# design.net
KiCad netlist of a schematic drawn in Altium Designer
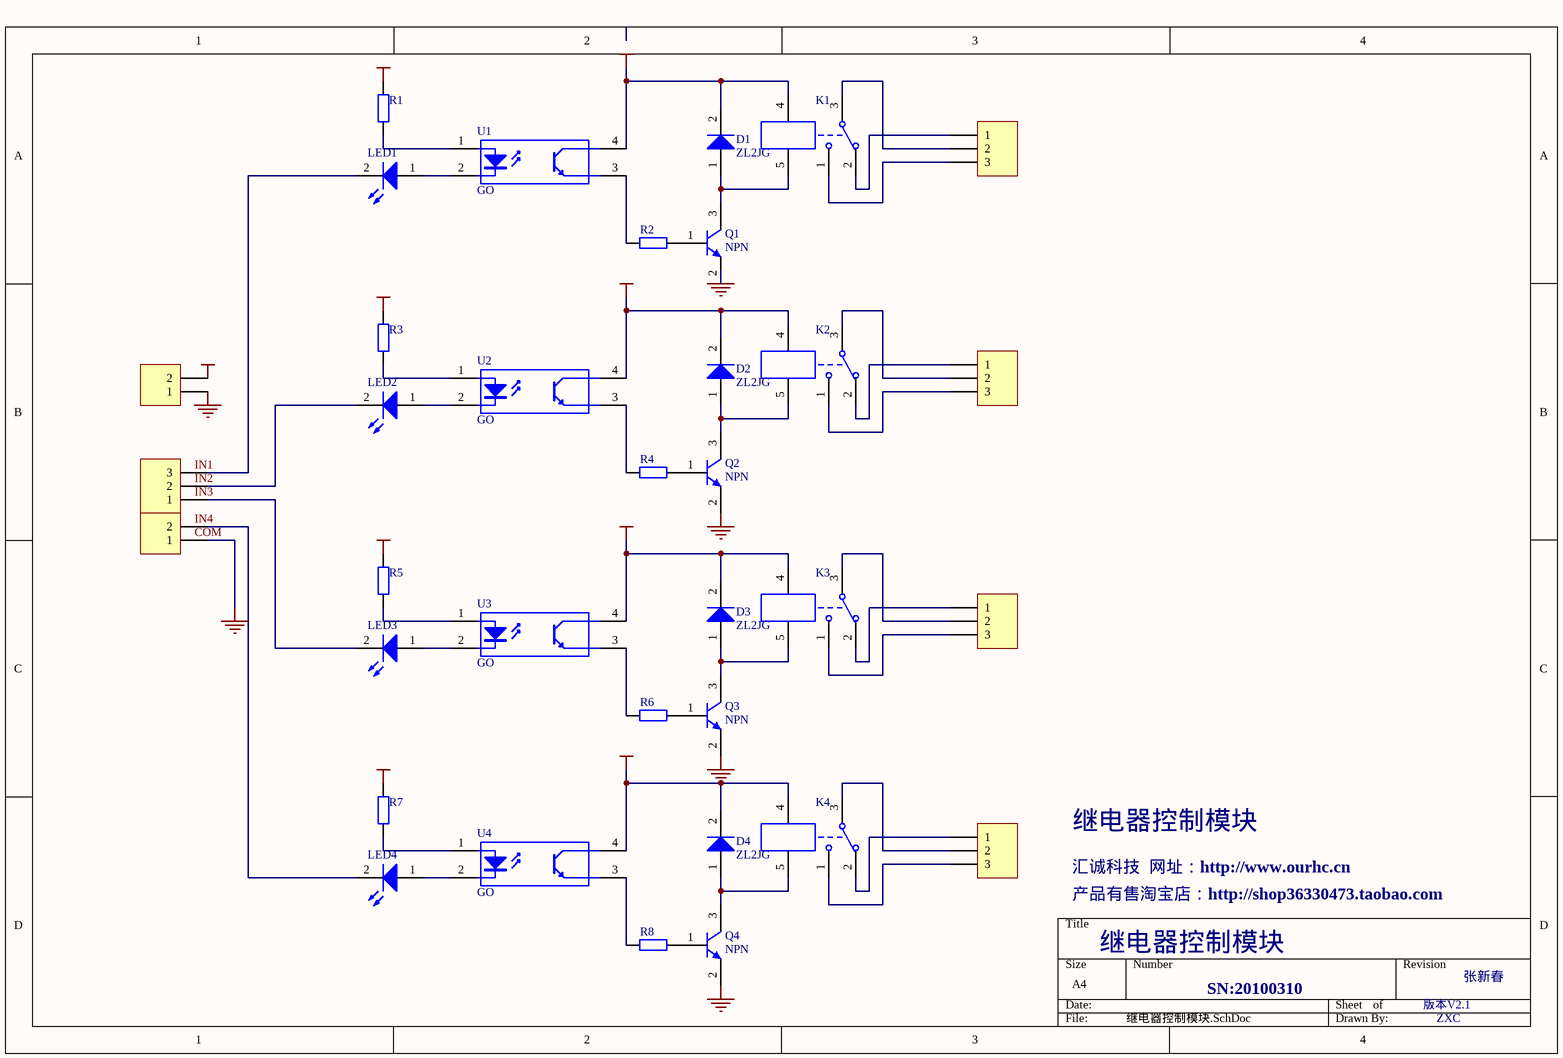
[diagram p0: 继电器控制模块.SchDoc]

(export (version "E")
  (design (tool "Eeschema 10.0.6"))
  (components
    (comp (ref "D1")
      (value "ZL2JG")
      (footprint "TPDR")
      (description "整流二极管")
      (fields (field (name "PUBLISHER") "Altium Limited"))
      (libsource (lib "zxcourhc") (part "ZL2JG"))
    )
    (comp (ref "D2")
      (value "ZL2JG")
      (footprint "TPDR")
      (description "整流二极管")
      (fields (field (name "PUBLISHER") "Altium Limited"))
      (libsource (lib "zxcourhc") (part "ZL2JG"))
    )
    (comp (ref "D3")
      (value "ZL2JG")
      (footprint "TPDR")
      (description "整流二极管")
      (fields (field (name "PUBLISHER") "Altium Limited"))
      (libsource (lib "zxcourhc") (part "ZL2JG"))
    )
    (comp (ref "D4")
      (value "ZL2JG")
      (footprint "TPDR")
      (description "整流二极管")
      (fields (field (name "PUBLISHER") "Altium Limited"))
      (libsource (lib "zxcourhc") (part "ZL2JG"))
    )
    (comp (ref "IN1")
      (value "PZ_3")
      (footprint "JK128_3")
      (description "排针——3")
      (fields (field (name "PUBLISHER") "Altium Limited"))
      (libsource (lib "zxcourhc") (part "PZ_3"))
    )
    (comp (ref "IN2")
      (value "PZ_2")
      (footprint "JK128_2")
      (description "排针——2")
      (fields (field (name "PUBLISHER") "Altium Limited"))
      (libsource (lib "zxcourhc") (part "PZ_2"))
    )
    (comp (ref "K1")
      (value "JDQYCK")
      (footprint "JQC-3F/T73")
      (description "继电器——1常开1常闭")
      (fields (field (name "PUBLISHER") "Altium Limited"))
      (libsource (lib "zxcourhc") (part "JDQYCK"))
    )
    (comp (ref "K2")
      (value "JDQYCK")
      (footprint "JQC-3F/T73")
      (description "继电器——1常开1常闭")
      (fields (field (name "PUBLISHER") "Altium Limited"))
      (libsource (lib "zxcourhc") (part "JDQYCK"))
    )
    (comp (ref "K3")
      (value "JDQYCK")
      (footprint "JQC-3F/T73")
      (description "继电器——1常开1常闭")
      (fields (field (name "PUBLISHER") "Altium Limited"))
      (libsource (lib "zxcourhc") (part "JDQYCK"))
    )
    (comp (ref "K4")
      (value "JDQYCK")
      (footprint "JQC-3F/T73")
      (description "继电器——1常开1常闭")
      (fields (field (name "PUBLISHER") "Altium Limited"))
      (libsource (lib "zxcourhc") (part "JDQYCK"))
    )
    (comp (ref "LED1")
      (value "~")
      (footprint "TP-0805-D")
      (description "发光二极管")
      (fields (field (name "PUBLISHER") "Altium Limited"))
      (libsource (lib "zxcourhc") (part "LED"))
    )
    (comp (ref "LED2")
      (value "~")
      (footprint "TP-0805-D")
      (description "发光二极管")
      (fields (field (name "PUBLISHER") "Altium Limited"))
      (libsource (lib "zxcourhc") (part "LED"))
    )
    (comp (ref "LED3")
      (value "~")
      (footprint "TP-0805-D")
      (description "发光二极管")
      (fields (field (name "PUBLISHER") "Altium Limited"))
      (libsource (lib "zxcourhc") (part "LED"))
    )
    (comp (ref "LED4")
      (value "~")
      (footprint "TP-0805-D")
      (description "发光二极管")
      (fields (field (name "PUBLISHER") "Altium Limited"))
      (libsource (lib "zxcourhc") (part "LED"))
    )
    (comp (ref "OUT1")
      (value "PZ_3")
      (footprint "JK128_3")
      (description "排针——3")
      (fields (field (name "PUBLISHER") "Altium Limited"))
      (libsource (lib "") (part "PZ_3_1"))
    )
    (comp (ref "OUT2")
      (value "PZ_3")
      (footprint "JK128_3")
      (description "排针——3")
      (fields (field (name "PUBLISHER") "Altium Limited"))
      (libsource (lib "") (part "PZ_3_1"))
    )
    (comp (ref "OUT3")
      (value "PZ_3")
      (footprint "JK128_3")
      (description "排针——3")
      (fields (field (name "PUBLISHER") "Altium Limited"))
      (libsource (lib "") (part "PZ_3_1"))
    )
    (comp (ref "OUT4")
      (value "PZ_3")
      (footprint "JK128_3")
      (description "排针——3")
      (fields (field (name "PUBLISHER") "Altium Limited"))
      (libsource (lib "") (part "PZ_3_1"))
    )
    (comp (ref "POWER")
      (value "PZ_2")
      (footprint "JK128_2")
      (description "排针——2")
      (fields (field (name "PUBLISHER") "Altium Limited"))
      (libsource (lib "zxcourhc") (part "PZ_2"))
    )
    (comp (ref "Q1")
      (value "NPN")
      (footprint "SO-G3")
      (description "NPN Bipolar Transistor")
      (fields (field (name "PUBLISHER") "Altium Limited"))
      (libsource (lib "Miscellaneous Devices") (part "NPN"))
    )
    (comp (ref "Q2")
      (value "NPN")
      (footprint "SO-G3")
      (description "NPN Bipolar Transistor")
      (fields (field (name "PUBLISHER") "Altium Limited"))
      (libsource (lib "Miscellaneous Devices") (part "NPN"))
    )
    (comp (ref "Q3")
      (value "NPN")
      (footprint "SO-G3")
      (description "NPN Bipolar Transistor")
      (fields (field (name "PUBLISHER") "Altium Limited"))
      (libsource (lib "Miscellaneous Devices") (part "NPN"))
    )
    (comp (ref "Q4")
      (value "NPN")
      (footprint "SO-G3")
      (description "NPN Bipolar Transistor")
      (fields (field (name "PUBLISHER") "Altium Limited"))
      (libsource (lib "Miscellaneous Devices") (part "NPN"))
    )
    (comp (ref "R1")
      (value "Res")
      (footprint "TP-0805-R")
      (description "电阻")
      (fields (field (name "PUBLISHER") "Altium Limited"))
      (libsource (lib "zxcourhc") (part "Res"))
    )
    (comp (ref "R2")
      (value "Res")
      (footprint "TP-0805-R")
      (description "电阻")
      (fields (field (name "PUBLISHER") "Altium Limited"))
      (libsource (lib "") (part "Res_1"))
    )
    (comp (ref "R3")
      (value "Res")
      (footprint "TP-0805-R")
      (description "电阻")
      (fields (field (name "PUBLISHER") "Altium Limited"))
      (libsource (lib "zxcourhc") (part "Res"))
    )
    (comp (ref "R4")
      (value "Res")
      (footprint "TP-0805-R")
      (description "电阻")
      (fields (field (name "PUBLISHER") "Altium Limited"))
      (libsource (lib "") (part "Res_1"))
    )
    (comp (ref "R5")
      (value "Res")
      (footprint "TP-0805-R")
      (description "电阻")
      (fields (field (name "PUBLISHER") "Altium Limited"))
      (libsource (lib "zxcourhc") (part "Res"))
    )
    (comp (ref "R6")
      (value "Res")
      (footprint "TP-0805-R")
      (description "电阻")
      (fields (field (name "PUBLISHER") "Altium Limited"))
      (libsource (lib "") (part "Res_1"))
    )
    (comp (ref "R7")
      (value "Res")
      (footprint "TP-0805-R")
      (description "电阻")
      (fields (field (name "PUBLISHER") "Altium Limited"))
      (libsource (lib "zxcourhc") (part "Res"))
    )
    (comp (ref "R8")
      (value "Res")
      (footprint "TP-0805-R")
      (description "电阻")
      (fields (field (name "PUBLISHER") "Altium Limited"))
      (libsource (lib "") (part "Res_1"))
    )
    (comp (ref "U1")
      (value "GO")
      (footprint "DIP-4")
      (description "光耦")
      (fields (field (name "PUBLISHER") "Altium Limited"))
      (libsource (lib "zxcourhc") (part "GO"))
    )
    (comp (ref "U2")
      (value "GO")
      (footprint "DIP-4")
      (description "光耦")
      (fields (field (name "PUBLISHER") "Altium Limited"))
      (libsource (lib "zxcourhc") (part "GO"))
    )
    (comp (ref "U3")
      (value "GO")
      (footprint "DIP-4")
      (description "光耦")
      (fields (field (name "PUBLISHER") "Altium Limited"))
      (libsource (lib "zxcourhc") (part "GO"))
    )
    (comp (ref "U4")
      (value "GO")
      (footprint "DIP-4")
      (description "光耦")
      (fields (field (name "PUBLISHER") "Altium Limited"))
      (libsource (lib "zxcourhc") (part "GO"))
    )
  )
  (nets
    (net (code "6") (name "GND") (class "Default")
      (node (ref "IN2") (pin "1") (pinfunction "1_1") (pintype "passive"))
      (node (ref "POWER") (pin "1") (pinfunction "1_1") (pintype "passive"))
      (node (ref "Q1") (pin "2") (pinfunction "E_2") (pintype "passive"))
      (node (ref "Q2") (pin "2") (pinfunction "E_2") (pintype "passive"))
      (node (ref "Q3") (pin "2") (pinfunction "E_2") (pintype "passive"))
      (node (ref "Q4") (pin "2") (pinfunction "E_2") (pintype "passive"))
    )
    (net (code "7") (name "Net-(D1-A)") (class "Default")
      (node (ref "D1") (pin "1") (pinfunction "A_1") (pintype "passive"))
      (node (ref "K1") (pin "5") (pinfunction "5_5") (pintype "passive"))
      (node (ref "Q1") (pin "3") (pinfunction "C_3") (pintype "passive"))
    )
    (net (code "8") (name "Net-(D2-A)") (class "Default")
      (node (ref "D2") (pin "1") (pinfunction "A_1") (pintype "passive"))
      (node (ref "K2") (pin "5") (pinfunction "5_5") (pintype "passive"))
      (node (ref "Q2") (pin "3") (pinfunction "C_3") (pintype "passive"))
    )
    (net (code "9") (name "Net-(D3-A)") (class "Default")
      (node (ref "D3") (pin "1") (pinfunction "A_1") (pintype "passive"))
      (node (ref "K3") (pin "5") (pinfunction "5_5") (pintype "passive"))
      (node (ref "Q3") (pin "3") (pinfunction "C_3") (pintype "passive"))
    )
    (net (code "10") (name "Net-(D4-A)") (class "Default")
      (node (ref "D4") (pin "1") (pinfunction "A_1") (pintype "passive"))
      (node (ref "K4") (pin "5") (pinfunction "5_5") (pintype "passive"))
      (node (ref "Q4") (pin "3") (pinfunction "C_3") (pintype "passive"))
    )
    (net (code "11") (name "Net-(K1-Pad1)") (class "Default")
      (node (ref "K1") (pin "1") (pinfunction "1_1") (pintype "passive"))
      (node (ref "OUT1") (pin "3") (pinfunction "3_3") (pintype "passive"))
    )
    (net (code "12") (name "Net-(K1-Pad2)") (class "Default")
      (node (ref "K1") (pin "2") (pinfunction "2_2") (pintype "passive"))
      (node (ref "OUT1") (pin "1") (pinfunction "1_1") (pintype "passive"))
    )
    (net (code "13") (name "Net-(K1-Pad3)") (class "Default")
      (node (ref "K1") (pin "3") (pinfunction "3_3") (pintype "passive"))
      (node (ref "OUT1") (pin "2") (pinfunction "2_2") (pintype "passive"))
    )
    (net (code "14") (name "Net-(K2-Pad1)") (class "Default")
      (node (ref "K2") (pin "1") (pinfunction "1_1") (pintype "passive"))
      (node (ref "OUT2") (pin "3") (pinfunction "3_3") (pintype "passive"))
    )
    (net (code "15") (name "Net-(K2-Pad2)") (class "Default")
      (node (ref "K2") (pin "2") (pinfunction "2_2") (pintype "passive"))
      (node (ref "OUT2") (pin "1") (pinfunction "1_1") (pintype "passive"))
    )
    (net (code "16") (name "Net-(K2-Pad3)") (class "Default")
      (node (ref "K2") (pin "3") (pinfunction "3_3") (pintype "passive"))
      (node (ref "OUT2") (pin "2") (pinfunction "2_2") (pintype "passive"))
    )
    (net (code "17") (name "Net-(K3-Pad1)") (class "Default")
      (node (ref "K3") (pin "1") (pinfunction "1_1") (pintype "passive"))
      (node (ref "OUT3") (pin "3") (pinfunction "3_3") (pintype "passive"))
    )
    (net (code "18") (name "Net-(K3-Pad2)") (class "Default")
      (node (ref "K3") (pin "2") (pinfunction "2_2") (pintype "passive"))
      (node (ref "OUT3") (pin "1") (pinfunction "1_1") (pintype "passive"))
    )
    (net (code "19") (name "Net-(K3-Pad3)") (class "Default")
      (node (ref "K3") (pin "3") (pinfunction "3_3") (pintype "passive"))
      (node (ref "OUT3") (pin "2") (pinfunction "2_2") (pintype "passive"))
    )
    (net (code "20") (name "Net-(K4-Pad1)") (class "Default")
      (node (ref "K4") (pin "1") (pinfunction "1_1") (pintype "passive"))
      (node (ref "OUT4") (pin "3") (pinfunction "3_3") (pintype "passive"))
    )
    (net (code "21") (name "Net-(K4-Pad2)") (class "Default")
      (node (ref "K4") (pin "2") (pinfunction "2_2") (pintype "passive"))
      (node (ref "OUT4") (pin "1") (pinfunction "1_1") (pintype "passive"))
    )
    (net (code "22") (name "Net-(K4-Pad3)") (class "Default")
      (node (ref "K4") (pin "3") (pinfunction "3_3") (pintype "passive"))
      (node (ref "OUT4") (pin "2") (pinfunction "2_2") (pintype "passive"))
    )
    (net (code "23") (name "Net-(LED1-A)") (class "Default")
      (node (ref "LED1") (pin "1") (pinfunction "A_1") (pintype "passive"))
      (node (ref "U1") (pin "2") (pinfunction "K_2") (pintype "passive"))
    )
    (net (code "24") (name "Net-(LED1-K)") (class "Default")
      (node (ref "IN1") (pin "3") (pinfunction "3_3") (pintype "passive"))
      (node (ref "LED1") (pin "2") (pinfunction "K_2") (pintype "passive"))
    )
    (net (code "25") (name "Net-(LED2-A)") (class "Default")
      (node (ref "LED2") (pin "1") (pinfunction "A_1") (pintype "passive"))
      (node (ref "U2") (pin "2") (pinfunction "K_2") (pintype "passive"))
    )
    (net (code "26") (name "Net-(LED2-K)") (class "Default")
      (node (ref "IN1") (pin "2") (pinfunction "2_2") (pintype "passive"))
      (node (ref "LED2") (pin "2") (pinfunction "K_2") (pintype "passive"))
    )
    (net (code "27") (name "Net-(LED3-A)") (class "Default")
      (node (ref "LED3") (pin "1") (pinfunction "A_1") (pintype "passive"))
      (node (ref "U3") (pin "2") (pinfunction "K_2") (pintype "passive"))
    )
    (net (code "28") (name "Net-(LED3-K)") (class "Default")
      (node (ref "IN1") (pin "1") (pinfunction "1_1") (pintype "passive"))
      (node (ref "LED3") (pin "2") (pinfunction "K_2") (pintype "passive"))
    )
    (net (code "29") (name "Net-(LED4-A)") (class "Default")
      (node (ref "LED4") (pin "1") (pinfunction "A_1") (pintype "passive"))
      (node (ref "U4") (pin "2") (pinfunction "K_2") (pintype "passive"))
    )
    (net (code "30") (name "Net-(LED4-K)") (class "Default")
      (node (ref "IN2") (pin "2") (pinfunction "2_2") (pintype "passive"))
      (node (ref "LED4") (pin "2") (pinfunction "K_2") (pintype "passive"))
    )
    (net (code "31") (name "Net-(Q1-B)") (class "Default")
      (node (ref "Q1") (pin "1") (pinfunction "B_1") (pintype "passive"))
      (node (ref "R2") (pin "1") (pinfunction "1_1") (pintype "passive"))
    )
    (net (code "32") (name "Net-(Q2-B)") (class "Default")
      (node (ref "Q2") (pin "1") (pinfunction "B_1") (pintype "passive"))
      (node (ref "R4") (pin "1") (pinfunction "1_1") (pintype "passive"))
    )
    (net (code "33") (name "Net-(Q3-B)") (class "Default")
      (node (ref "Q3") (pin "1") (pinfunction "B_1") (pintype "passive"))
      (node (ref "R6") (pin "1") (pinfunction "1_1") (pintype "passive"))
    )
    (net (code "34") (name "Net-(Q4-B)") (class "Default")
      (node (ref "Q4") (pin "1") (pinfunction "B_1") (pintype "passive"))
      (node (ref "R8") (pin "1") (pinfunction "1_1") (pintype "passive"))
    )
    (net (code "35") (name "Net-(U1-A)") (class "Default")
      (node (ref "R1") (pin "1") (pinfunction "1_1") (pintype "passive"))
      (node (ref "U1") (pin "1") (pinfunction "A_1") (pintype "passive"))
    )
    (net (code "36") (name "Net-(U1-E)") (class "Default")
      (node (ref "R2") (pin "2") (pinfunction "2_2") (pintype "passive"))
      (node (ref "U1") (pin "3") (pinfunction "E_3") (pintype "passive"))
    )
    (net (code "37") (name "Net-(U2-A)") (class "Default")
      (node (ref "R3") (pin "1") (pinfunction "1_1") (pintype "passive"))
      (node (ref "U2") (pin "1") (pinfunction "A_1") (pintype "passive"))
    )
    (net (code "38") (name "Net-(U2-E)") (class "Default")
      (node (ref "R4") (pin "2") (pinfunction "2_2") (pintype "passive"))
      (node (ref "U2") (pin "3") (pinfunction "E_3") (pintype "passive"))
    )
    (net (code "39") (name "Net-(U3-A)") (class "Default")
      (node (ref "R5") (pin "1") (pinfunction "1_1") (pintype "passive"))
      (node (ref "U3") (pin "1") (pinfunction "A_1") (pintype "passive"))
    )
    (net (code "40") (name "Net-(U3-E)") (class "Default")
      (node (ref "R6") (pin "2") (pinfunction "2_2") (pintype "passive"))
      (node (ref "U3") (pin "3") (pinfunction "E_3") (pintype "passive"))
    )
    (net (code "41") (name "Net-(U4-A)") (class "Default")
      (node (ref "R7") (pin "1") (pinfunction "1_1") (pintype "passive"))
      (node (ref "U4") (pin "1") (pinfunction "A_1") (pintype "passive"))
    )
    (net (code "42") (name "Net-(U4-E)") (class "Default")
      (node (ref "R8") (pin "2") (pinfunction "2_2") (pintype "passive"))
      (node (ref "U4") (pin "3") (pinfunction "E_3") (pintype "passive"))
    )
    (net (code "43") (name "VCC") (class "Default")
      (node (ref "D1") (pin "2") (pinfunction "K_2") (pintype "passive"))
      (node (ref "D2") (pin "2") (pinfunction "K_2") (pintype "passive"))
      (node (ref "D3") (pin "2") (pinfunction "K_2") (pintype "passive"))
      (node (ref "D4") (pin "2") (pinfunction "K_2") (pintype "passive"))
      (node (ref "K1") (pin "4") (pinfunction "4_4") (pintype "passive"))
      (node (ref "K2") (pin "4") (pinfunction "4_4") (pintype "passive"))
      (node (ref "K3") (pin "4") (pinfunction "4_4") (pintype "passive"))
      (node (ref "K4") (pin "4") (pinfunction "4_4") (pintype "passive"))
      (node (ref "POWER") (pin "2") (pinfunction "2_2") (pintype "passive"))
      (node (ref "R1") (pin "2") (pinfunction "2_2") (pintype "passive"))
      (node (ref "R3") (pin "2") (pinfunction "2_2") (pintype "passive"))
      (node (ref "R5") (pin "2") (pinfunction "2_2") (pintype "passive"))
      (node (ref "R7") (pin "2") (pinfunction "2_2") (pintype "passive"))
      (node (ref "U1") (pin "4") (pinfunction "C_4") (pintype "passive"))
      (node (ref "U2") (pin "4") (pinfunction "C_4") (pintype "passive"))
      (node (ref "U3") (pin "4") (pinfunction "C_4") (pintype "passive"))
      (node (ref "U4") (pin "4") (pinfunction "C_4") (pintype "passive"))
    )
  )
)
